# esp12_Epaper4_2.net
KiCad netlist of a schematic drawn in EAGLE
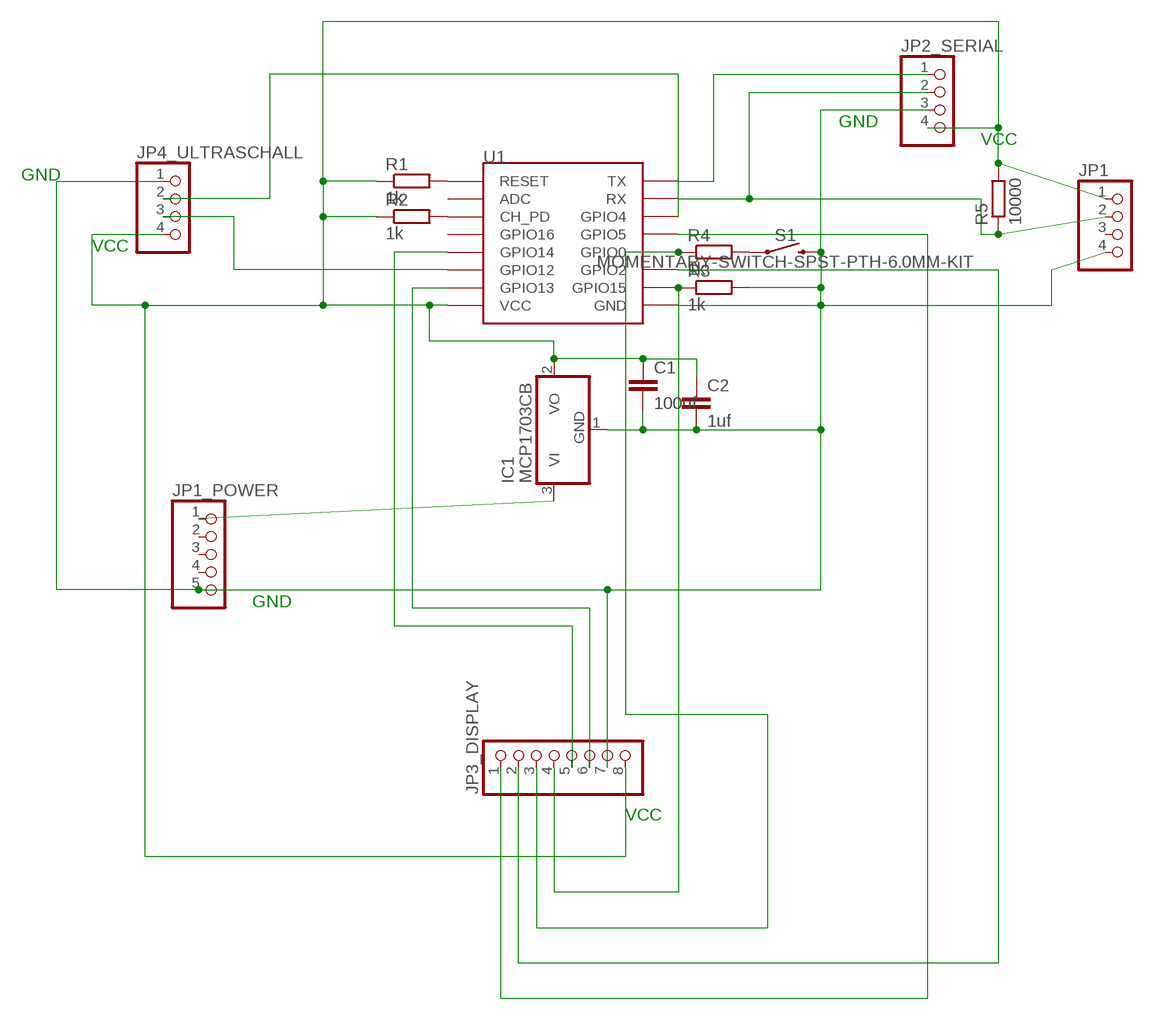
[diagram p0: schematic, sheet 1]

(export (version "E")
  (design (tool "Eeschema 10.0.6"))
  (components
    (comp (ref "C1")
      (value "100uf")
      (footprint "eagle-import:C025-050X050")
      (libsource (lib "eagle-import") (part "C-EU025-050X050"))
    )
    (comp (ref "C2")
      (value "1uf")
      (footprint "eagle-import:C025-050X050")
      (libsource (lib "eagle-import") (part "C-EU025-050X050"))
    )
    (comp (ref "IC1")
      (value "MCP1703CB")
      (footprint "eagle-import:SOT23")
      (libsource (lib "eagle-import") (part "MCP1703CB"))
    )
    (comp (ref "JP1")
      (value "PINHD-1X4")
      (footprint "eagle-import:1X04")
      (libsource (lib "eagle-import") (part "PINHD-1X4"))
    )
    (comp (ref "JP1_POWER")
      (value "PINHD-1X5")
      (footprint "eagle-import:1X05")
      (libsource (lib "eagle-import") (part "PINHD-1X5"))
    )
    (comp (ref "JP2_SERIAL")
      (value "PINHD-1X4/90")
      (footprint "eagle-import:1X04_90")
      (libsource (lib "eagle-import") (part "PINHD-1X4/90"))
    )
    (comp (ref "JP3_DISPLAY")
      (value "PINHD-1X8/90")
      (footprint "eagle-import:1X08_90")
      (libsource (lib "eagle-import") (part "PINHD-1X8/90"))
    )
    (comp (ref "JP4_ULTRASCHALL")
      (value "PINHD-1X4")
      (footprint "eagle-import:1X04")
      (libsource (lib "eagle-import") (part "PINHD-1X4"))
    )
    (comp (ref "R1")
      (value "1k")
      (footprint "eagle-import:R1206")
      (libsource (lib "eagle-import") (part "R-EU_R1206"))
    )
    (comp (ref "R2")
      (value "1k")
      (footprint "eagle-import:R1206")
      (libsource (lib "eagle-import") (part "R-EU_R1206"))
    )
    (comp (ref "R3")
      (value "1k")
      (footprint "eagle-import:R1206")
      (libsource (lib "eagle-import") (part "R-EU_R1206"))
    )
    (comp (ref "R4")
      (value "1k")
      (footprint "eagle-import:R1206")
      (libsource (lib "eagle-import") (part "R-EU_R1206"))
    )
    (comp (ref "R5")
      (value "10000")
      (footprint "eagle-import:M1206")
      (libsource (lib "eagle-import") (part "R-EU_M1206"))
    )
    (comp (ref "S1")
      (value "MOMENTARY-SWITCH-SPST-PTH-6.0MM-KIT")
      (footprint "eagle-import:TACTILE_SWITCH_PTH_6.0MM_KIT")
      (libsource (lib "eagle-import") (part "MOMENTARY-SWITCH-SPST-PTH-6.0MM-KIT"))
    )
    (comp (ref "U1")
      (value "ESP12")
      (footprint "eagle-import:ESP12")
      (libsource (lib "eagle-import") (part "ESP12"))
    )
  )
  (nets
    (net (code "1") (name "Net-(IC1-GND)") (class "Default")
      (node (ref "C1") (pin "2") (pinfunction "2_2") (pintype "passive"))
      (node (ref "C2") (pin "2") (pinfunction "2_2") (pintype "passive"))
      (node (ref "IC1") (pin "1") (pinfunction "GND_1") (pintype "passive"))
      (node (ref "JP1") (pin "4") (pinfunction "4_4") (pintype "passive"))
      (node (ref "JP1_POWER") (pin "5") (pinfunction "5_5") (pintype "passive"))
      (node (ref "JP2_SERIAL") (pin "3") (pinfunction "3_3") (pintype "passive"))
      (node (ref "JP3_DISPLAY") (pin "7") (pinfunction "7_7") (pintype "passive"))
      (node (ref "JP4_ULTRASCHALL") (pin "1") (pinfunction "1_1") (pintype "passive"))
      (node (ref "R3") (pin "2") (pinfunction "2_2") (pintype "passive"))
      (node (ref "S1") (pin "3") (pinfunction "2_3") (pintype "passive"))
      (node (ref "U1") (pin "GND") (pinfunction "GND_GND") (pintype "bidirectional"))
    )
    (net (code "2") (name "Net-(IC1-VI)") (class "Default")
      (node (ref "IC1") (pin "3") (pinfunction "VI_3") (pintype "input"))
      (node (ref "JP1_POWER") (pin "1") (pinfunction "1_1") (pintype "passive"))
    )
    (net (code "3") (name "Net-(IC1-VO)") (class "Default")
      (node (ref "C1") (pin "1") (pinfunction "1_1") (pintype "passive"))
      (node (ref "C2") (pin "1") (pinfunction "1_1") (pintype "passive"))
      (node (ref "IC1") (pin "2") (pinfunction "VO_2") (pintype "passive"))
      (node (ref "JP1") (pin "1") (pinfunction "1_1") (pintype "passive"))
      (node (ref "JP2_SERIAL") (pin "4") (pinfunction "4_4") (pintype "passive"))
      (node (ref "JP3_DISPLAY") (pin "8") (pinfunction "8_8") (pintype "passive"))
      (node (ref "JP4_ULTRASCHALL") (pin "4") (pinfunction "4_4") (pintype "passive"))
      (node (ref "R1") (pin "1") (pinfunction "1_1") (pintype "passive"))
      (node (ref "R2") (pin "1") (pinfunction "1_1") (pintype "passive"))
      (node (ref "R5") (pin "2") (pinfunction "2_2") (pintype "passive"))
      (node (ref "U1") (pin "VCC") (pinfunction "VCC_VCC") (pintype "bidirectional"))
    )
    (net (code "4") (name "Net-(JP1-Pad2)") (class "Default")
      (node (ref "JP1") (pin "2") (pinfunction "2_2") (pintype "passive"))
      (node (ref "JP2_SERIAL") (pin "2") (pinfunction "2_2") (pintype "passive"))
      (node (ref "R5") (pin "1") (pinfunction "1_1") (pintype "passive"))
      (node (ref "U1") (pin "RX") (pinfunction "RX_RX") (pintype "bidirectional"))
    )
    (net (code "5") (name "Net-(JP2_SERIAL-Pad1)") (class "Default")
      (node (ref "JP2_SERIAL") (pin "1") (pinfunction "1_1") (pintype "passive"))
      (node (ref "U1") (pin "TX") (pinfunction "TX_TX") (pintype "bidirectional"))
    )
    (net (code "6") (name "Net-(JP3_DISPLAY-Pad1)") (class "Default")
      (node (ref "JP3_DISPLAY") (pin "1") (pinfunction "1_1") (pintype "passive"))
      (node (ref "U1") (pin "GPIO5") (pinfunction "GPIO5_GPIO5") (pintype "bidirectional"))
    )
    (net (code "7") (name "Net-(JP3_DISPLAY-Pad2)") (class "Default")
      (node (ref "JP3_DISPLAY") (pin "2") (pinfunction "2_2") (pintype "passive"))
      (node (ref "U1") (pin "GPIO2") (pinfunction "GPIO2_GPIO2") (pintype "bidirectional"))
    )
    (net (code "8") (name "Net-(JP3_DISPLAY-Pad3)") (class "Default")
      (node (ref "JP3_DISPLAY") (pin "3") (pinfunction "3_3") (pintype "passive"))
      (node (ref "R4") (pin "1") (pinfunction "1_1") (pintype "passive"))
      (node (ref "U1") (pin "GPIO0") (pinfunction "GPIO0_GPIO0") (pintype "bidirectional"))
    )
    (net (code "9") (name "Net-(JP3_DISPLAY-Pad4)") (class "Default")
      (node (ref "JP3_DISPLAY") (pin "4") (pinfunction "4_4") (pintype "passive"))
      (node (ref "R3") (pin "1") (pinfunction "1_1") (pintype "passive"))
      (node (ref "U1") (pin "GPIO15") (pinfunction "GPIO15_GPIO15") (pintype "bidirectional"))
    )
    (net (code "10") (name "Net-(JP3_DISPLAY-Pad5)") (class "Default")
      (node (ref "JP3_DISPLAY") (pin "5") (pinfunction "5_5") (pintype "passive"))
      (node (ref "U1") (pin "GPIO14") (pinfunction "GPIO14_GPIO14") (pintype "bidirectional"))
    )
    (net (code "11") (name "Net-(JP3_DISPLAY-Pad6)") (class "Default")
      (node (ref "JP3_DISPLAY") (pin "6") (pinfunction "6_6") (pintype "passive"))
      (node (ref "U1") (pin "GPIO13") (pinfunction "GPIO13_GPIO13") (pintype "bidirectional"))
    )
    (net (code "12") (name "Net-(JP4_ULTRASCHALL-Pad2)") (class "Default")
      (node (ref "JP4_ULTRASCHALL") (pin "2") (pinfunction "2_2") (pintype "passive"))
      (node (ref "U1") (pin "GPIO4") (pinfunction "GPIO4_GPIO4") (pintype "bidirectional"))
    )
    (net (code "13") (name "Net-(JP4_ULTRASCHALL-Pad3)") (class "Default")
      (node (ref "JP4_ULTRASCHALL") (pin "3") (pinfunction "3_3") (pintype "passive"))
      (node (ref "U1") (pin "GPIO12") (pinfunction "GPIO12_GPIO12") (pintype "bidirectional"))
    )
    (net (code "14") (name "Net-(R1-Pad2)") (class "Default")
      (node (ref "R1") (pin "2") (pinfunction "2_2") (pintype "passive"))
      (node (ref "U1") (pin "RESET") (pinfunction "RESET_RESET") (pintype "bidirectional"))
    )
    (net (code "15") (name "Net-(R2-Pad2)") (class "Default")
      (node (ref "R2") (pin "2") (pinfunction "2_2") (pintype "passive"))
      (node (ref "U1") (pin "CH_PD") (pinfunction "CH_PD_CH_PD") (pintype "bidirectional"))
    )
    (net (code "16") (name "Net-(R4-Pad2)") (class "Default")
      (node (ref "R4") (pin "2") (pinfunction "2_2") (pintype "passive"))
      (node (ref "S1") (pin "1") (pinfunction "1_1") (pintype "passive"))
    )
    (net (code "17") (name "unconnected-(JP1-Pad3)") (class "Default")
      (node (ref "JP1") (pin "3") (pinfunction "3_3") (pintype "passive"))
    )
    (net (code "18") (name "unconnected-(JP1_POWER-Pad2)") (class "Default")
      (node (ref "JP1_POWER") (pin "2") (pinfunction "2_2") (pintype "passive"))
    )
    (net (code "19") (name "unconnected-(JP1_POWER-Pad3)") (class "Default")
      (node (ref "JP1_POWER") (pin "3") (pinfunction "3_3") (pintype "passive"))
    )
    (net (code "20") (name "unconnected-(JP1_POWER-Pad4)") (class "Default")
      (node (ref "JP1_POWER") (pin "4") (pinfunction "4_4") (pintype "passive"))
    )
    (net (code "21") (name "unconnected-(U1-PadADC)") (class "Default")
      (node (ref "U1") (pin "ADC") (pinfunction "ADC_ADC") (pintype "bidirectional"))
    )
    (net (code "22") (name "unconnected-(U1-PadGPIO16)") (class "Default")
      (node (ref "U1") (pin "GPIO16") (pinfunction "GPIO16_GPIO16") (pintype "bidirectional"))
    )
  )
)
